# LoggerAVR.net
KiCad netlist of a schematic drawn in EAGLE
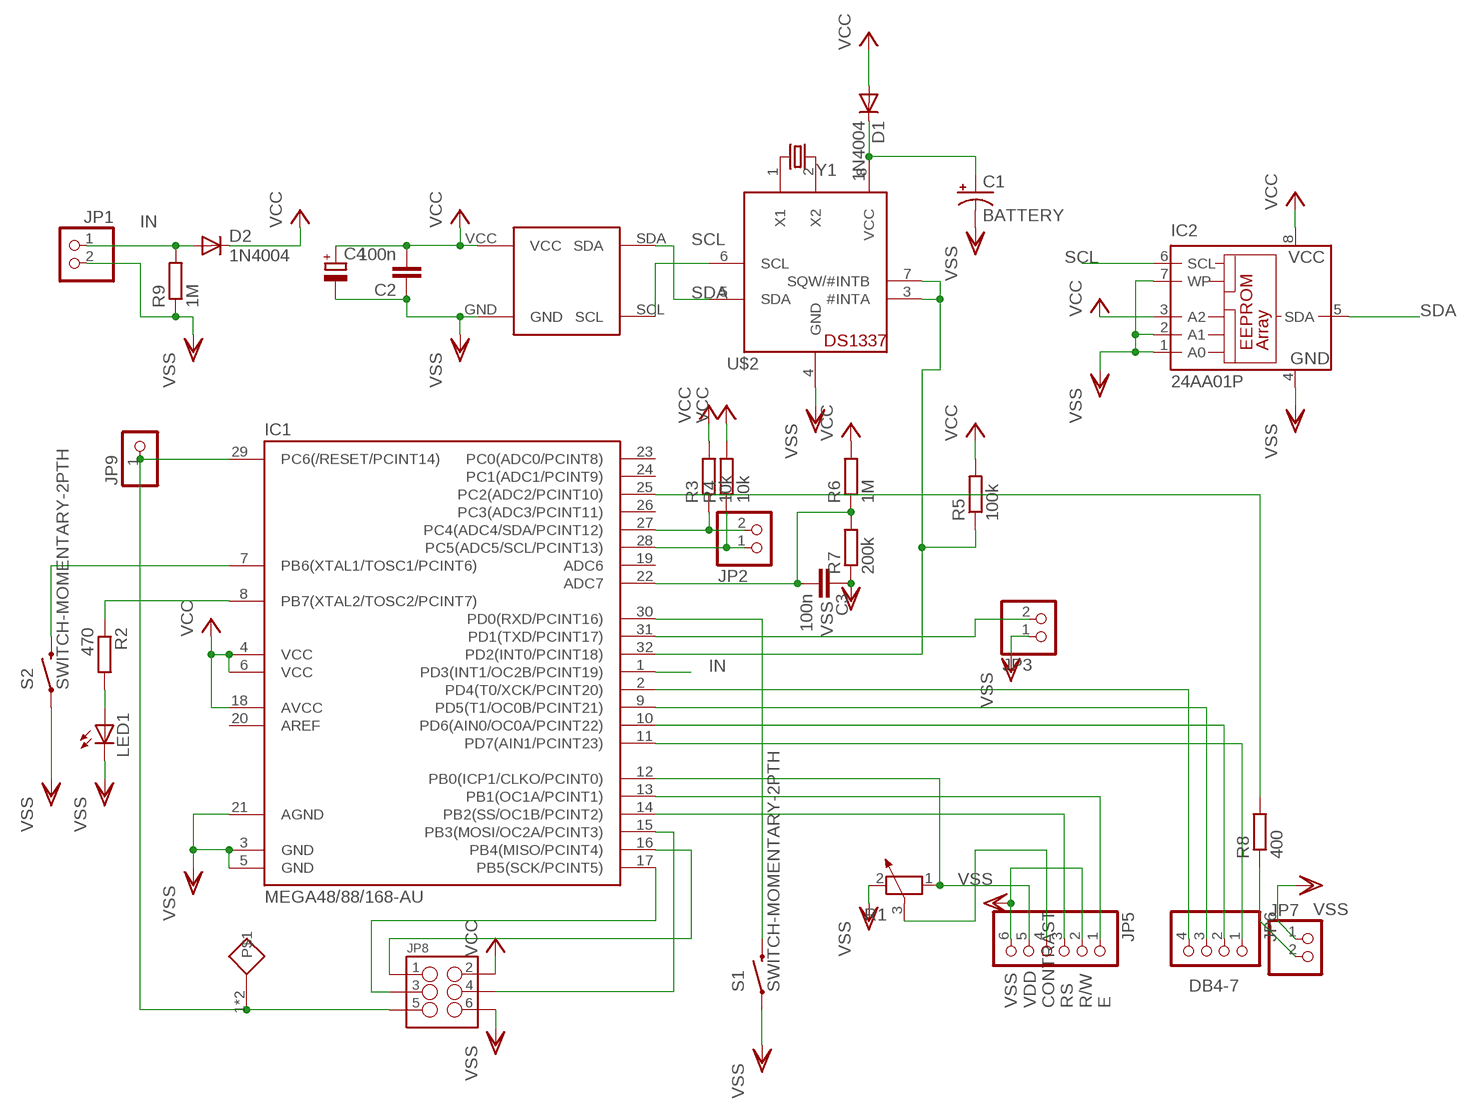
[diagram p0: schematic, sheet 1]

(export (version "E")
  (design (tool "Eeschema 10.0.6"))
  (components
    (comp (ref "C1")
      (value "BATTERY")
      (footprint "eagle-import:ETR2")
      (libsource (lib "eagle-import") (part "CPOL-USETR2"))
    )
    (comp (ref "C2")
      (value "100n")
      (footprint "eagle-import:C1206")
      (libsource (lib "eagle-import") (part "C-EUC1206"))
    )
    (comp (ref "C3")
      (value "100n")
      (footprint "eagle-import:C1206")
      (libsource (lib "eagle-import") (part "C-EUC1206"))
    )
    (comp (ref "C4")
      (value "CPOL-EUE22-9AXIAL")
      (footprint "eagle-import:E22-9")
      (libsource (lib "eagle-import") (part "CPOL-EUE22-9AXIAL"))
    )
    (comp (ref "D1")
      (value "1N4004")
      (footprint "eagle-import:DO41-10")
      (libsource (lib "eagle-import") (part "1N4004"))
    )
    (comp (ref "D2")
      (value "1N4004")
      (footprint "eagle-import:DO41-10")
      (libsource (lib "eagle-import") (part "1N4004"))
    )
    (comp (ref "IC1")
      (value "MEGA48/88/168-AU")
      (footprint "eagle-import:TQFP32-08")
      (libsource (lib "eagle-import") (part "MEGA48/88/168-AU"))
    )
    (comp (ref "IC2")
      (value "24AA01P")
      (footprint "eagle-import:DIL8")
      (libsource (lib "eagle-import") (part "24PAA01"))
    )
    (comp (ref "JP1")
      (value "PINHD-1X2")
      (footprint "eagle-import:1X02")
      (libsource (lib "eagle-import") (part "PINHD-1X2"))
    )
    (comp (ref "JP2")
      (value "PINHD-1X2")
      (footprint "eagle-import:1X02")
      (libsource (lib "eagle-import") (part "PINHD-1X2"))
    )
    (comp (ref "JP3")
      (value "PINHD-1X2")
      (footprint "eagle-import:1X02")
      (libsource (lib "eagle-import") (part "PINHD-1X2"))
    )
    (comp (ref "JP5")
      (value "PINHD-1X6")
      (footprint "eagle-import:1X06")
      (libsource (lib "eagle-import") (part "PINHD-1X6"))
    )
    (comp (ref "JP6")
      (value "PINHD-1X4")
      (footprint "eagle-import:1X04")
      (libsource (lib "eagle-import") (part "PINHD-1X4"))
    )
    (comp (ref "JP7")
      (value "PINHD-1X2")
      (footprint "eagle-import:1X02")
      (libsource (lib "eagle-import") (part "PINHD-1X2"))
    )
    (comp (ref "JP8")
      (value "M03X2SHROUD")
      (footprint "eagle-import:2X3-SHROUDED")
      (libsource (lib "eagle-import") (part "M03X2SHROUD"))
    )
    (comp (ref "JP9")
      (value "PINHD-1X1")
      (footprint "eagle-import:1X01")
      (libsource (lib "eagle-import") (part "PINHD-1X1"))
    )
    (comp (ref "LED1")
      (value "LEDSML1206")
      (footprint "eagle-import:SML1206")
      (libsource (lib "eagle-import") (part "LEDSML1206"))
    )
    (comp (ref "R1")
      (value "POTENTIOMETER_PT-10")
      (footprint "eagle-import:PT-10")
      (libsource (lib "eagle-import") (part "POTENTIOMETER_PT-10"))
    )
    (comp (ref "R2")
      (value "470")
      (footprint "eagle-import:M1206")
      (libsource (lib "eagle-import") (part "R-EU_M1206"))
    )
    (comp (ref "R3")
      (value "10k")
      (footprint "eagle-import:M1206")
      (libsource (lib "eagle-import") (part "R-EU_M1206"))
    )
    (comp (ref "R4")
      (value "10k")
      (footprint "eagle-import:M1206")
      (libsource (lib "eagle-import") (part "R-EU_M1206"))
    )
    (comp (ref "R5")
      (value "100k")
      (footprint "eagle-import:M1206")
      (libsource (lib "eagle-import") (part "R-EU_M1206"))
    )
    (comp (ref "R6")
      (value "1M")
      (footprint "eagle-import:M1206")
      (libsource (lib "eagle-import") (part "R-EU_M1206"))
    )
    (comp (ref "R7")
      (value "200k")
      (footprint "eagle-import:M1206")
      (libsource (lib "eagle-import") (part "R-EU_M1206"))
    )
    (comp (ref "R8")
      (value "400")
      (footprint "eagle-import:M1206")
      (libsource (lib "eagle-import") (part "R-EU_M1206"))
    )
    (comp (ref "R9")
      (value "1M")
      (footprint "eagle-import:M1206")
      (libsource (lib "eagle-import") (part "R-EU_M1206"))
    )
    (comp (ref "S1")
      (value "SWITCH-MOMENTARY-2PTH")
      (footprint "eagle-import:TACTILE-PTH")
      (libsource (lib "eagle-import") (part "SWITCH-MOMENTARY-2PTH"))
    )
    (comp (ref "S2")
      (value "SWITCH-MOMENTARY-2PTH")
      (footprint "eagle-import:TACTILE-PTH")
      (libsource (lib "eagle-import") (part "SWITCH-MOMENTARY-2PTH"))
    )
    (comp (ref "U$1")
      (value "HYT939")
      (footprint "eagle-import:TO39")
      (libsource (lib "eagle-import") (part "HYT939"))
    )
    (comp (ref "U$2")
      (value "DS1337")
      (footprint "eagle-import:DIL08-ROUND")
      (libsource (lib "eagle-import") (part "DS1337"))
    )
    (comp (ref "U$3")
      (value "0 - Jump")
      (footprint "eagle-import:R1206")
      (libsource (lib "eagle-import") (part "O-OHMJUMPER"))
    )
    (comp (ref "Y1")
      (value "CRYSTAL32-SMD")
      (footprint "eagle-import:CRYSTAL-32KHZ-SMD")
      (libsource (lib "eagle-import") (part "CRYSTAL32-SMD"))
    )
  )
  (nets
    (net (code "1") (name "/IN") (class "Default")
      (node (ref "D2") (pin "A") (pinfunction "A_A") (pintype "passive"))
      (node (ref "IC1") (pin "1") (pinfunction "PD3(INT1/OC2B/PCINT19)_1") (pintype "bidirectional"))
      (node (ref "JP1") (pin "1") (pinfunction "1_1") (pintype "passive"))
      (node (ref "R9") (pin "2") (pinfunction "2_2") (pintype "passive"))
    )
    (net (code "2") (name "/SCL") (class "Default")
      (node (ref "IC1") (pin "28") (pinfunction "PC5(ADC5/SCL/PCINT13)_28") (pintype "bidirectional"))
      (node (ref "IC2") (pin "6") (pinfunction "SCL_6") (pintype "input"))
      (node (ref "JP2") (pin "1") (pinfunction "1_1") (pintype "passive"))
      (node (ref "R4") (pin "1") (pinfunction "1_1") (pintype "passive"))
      (node (ref "U$1") (pin "SCL") (pinfunction "SCL_SCL") (pintype "bidirectional"))
      (node (ref "U$2") (pin "6") (pinfunction "SCL_6") (pintype "bidirectional"))
    )
    (net (code "3") (name "/SDA") (class "Default")
      (node (ref "IC1") (pin "27") (pinfunction "PC4(ADC4/SDA/PCINT12)_27") (pintype "bidirectional"))
      (node (ref "IC2") (pin "5") (pinfunction "SDA_5") (pintype "bidirectional"))
      (node (ref "JP2") (pin "2") (pinfunction "2_2") (pintype "passive"))
      (node (ref "R3") (pin "1") (pinfunction "1_1") (pintype "passive"))
      (node (ref "U$1") (pin "SDA") (pinfunction "SDA_SDA") (pintype "bidirectional"))
      (node (ref "U$2") (pin "5") (pinfunction "SDA_5") (pintype "bidirectional"))
    )
    (net (code "4") (name "Net-(IC1-ADC7)") (class "Default")
      (node (ref "C3") (pin "2") (pinfunction "2_2") (pintype "passive"))
      (node (ref "IC1") (pin "22") (pinfunction "ADC7_22") (pintype "passive"))
      (node (ref "R6") (pin "1") (pinfunction "1_1") (pintype "passive"))
      (node (ref "R7") (pin "2") (pinfunction "2_2") (pintype "passive"))
    )
    (net (code "5") (name "Net-(IC1-PB0(ICP1{slash}CLKO{slash}PCINT0))") (class "Default")
      (node (ref "IC1") (pin "12") (pinfunction "PB0(ICP1/CLKO/PCINT0)_12") (pintype "bidirectional"))
      (node (ref "JP5") (pin "5") (pinfunction "5_5") (pintype "passive"))
      (node (ref "R1") (pin "1") (pinfunction "1_1") (pintype "passive"))
    )
    (net (code "6") (name "Net-(IC1-PB1(OC1A{slash}PCINT1))") (class "Default")
      (node (ref "IC1") (pin "13") (pinfunction "PB1(OC1A/PCINT1)_13") (pintype "bidirectional"))
      (node (ref "JP5") (pin "1") (pinfunction "1_1") (pintype "passive"))
    )
    (net (code "7") (name "Net-(IC1-PB2(SS{slash}OC1B{slash}PCINT2))") (class "Default")
      (node (ref "IC1") (pin "14") (pinfunction "PB2(SS/OC1B/PCINT2)_14") (pintype "bidirectional"))
      (node (ref "JP5") (pin "3") (pinfunction "3_3") (pintype "passive"))
    )
    (net (code "8") (name "Net-(IC1-PB3(MOSI{slash}OC2A{slash}PCINT3))") (class "Default")
      (node (ref "IC1") (pin "15") (pinfunction "PB3(MOSI/OC2A/PCINT3)_15") (pintype "bidirectional"))
      (node (ref "JP8") (pin "4") (pinfunction "4_4") (pintype "bidirectional"))
    )
    (net (code "9") (name "Net-(IC1-PB4(MISO{slash}PCINT4))") (class "Default")
      (node (ref "IC1") (pin "16") (pinfunction "PB4(MISO/PCINT4)_16") (pintype "bidirectional"))
      (node (ref "JP8") (pin "1") (pinfunction "1_1") (pintype "bidirectional"))
    )
    (net (code "10") (name "Net-(IC1-PB5(SCK{slash}PCINT5))") (class "Default")
      (node (ref "IC1") (pin "17") (pinfunction "PB5(SCK/PCINT5)_17") (pintype "bidirectional"))
      (node (ref "JP8") (pin "3") (pinfunction "3_3") (pintype "bidirectional"))
    )
    (net (code "11") (name "Net-(IC1-PB6(XTAL1{slash}TOSC1{slash}PCINT6))") (class "Default")
      (node (ref "IC1") (pin "7") (pinfunction "PB6(XTAL1/TOSC1/PCINT6)_7") (pintype "bidirectional"))
      (node (ref "S2") (pin "3") (pinfunction "2_3") (pintype "passive"))
      (node (ref "S2") (pin "4") (pinfunction "2_4") (pintype "passive"))
    )
    (net (code "12") (name "Net-(IC1-PB7(XTAL2{slash}TOSC2{slash}PCINT7))") (class "Default")
      (node (ref "IC1") (pin "8") (pinfunction "PB7(XTAL2/TOSC2/PCINT7)_8") (pintype "bidirectional"))
      (node (ref "R2") (pin "1") (pinfunction "1_1") (pintype "passive"))
    )
    (net (code "13") (name "Net-(IC1-PC2(ADC2{slash}PCINT10))") (class "Default")
      (node (ref "IC1") (pin "25") (pinfunction "PC2(ADC2/PCINT10)_25") (pintype "bidirectional"))
      (node (ref "R8") (pin "2") (pinfunction "2_2") (pintype "passive"))
    )
    (net (code "14") (name "Net-(IC1-PC6({slash}RESET{slash}PCINT14))") (class "Default")
      (node (ref "IC1") (pin "29") (pinfunction "PC6(/RESET/PCINT14)_29") (pintype "bidirectional"))
      (node (ref "JP8") (pin "5") (pinfunction "5_5") (pintype "bidirectional"))
      (node (ref "JP9") (pin "1") (pinfunction "1_1") (pintype "passive"))
      (node (ref "U$3") (pin "1") (pinfunction "P$1_1") (pintype "bidirectional"))
      (node (ref "U$3") (pin "2") (pinfunction "P$1_2") (pintype "bidirectional"))
    )
    (net (code "15") (name "Net-(IC1-PD0(RXD{slash}PCINT16))") (class "Default")
      (node (ref "IC1") (pin "30") (pinfunction "PD0(RXD/PCINT16)_30") (pintype "bidirectional"))
      (node (ref "S1") (pin "3") (pinfunction "2_3") (pintype "passive"))
      (node (ref "S1") (pin "4") (pinfunction "2_4") (pintype "passive"))
    )
    (net (code "16") (name "Net-(IC1-PD1(TXD{slash}PCINT17))") (class "Default")
      (node (ref "IC1") (pin "31") (pinfunction "PD1(TXD/PCINT17)_31") (pintype "bidirectional"))
      (node (ref "JP3") (pin "2") (pinfunction "2_2") (pintype "passive"))
    )
    (net (code "17") (name "Net-(IC1-PD2(INT0{slash}PCINT18))") (class "Default")
      (node (ref "IC1") (pin "32") (pinfunction "PD2(INT0/PCINT18)_32") (pintype "bidirectional"))
      (node (ref "R5") (pin "1") (pinfunction "1_1") (pintype "passive"))
      (node (ref "U$2") (pin "3") (pinfunction "#INTA_3") (pintype "output"))
      (node (ref "U$2") (pin "7") (pinfunction "SQW/#INTB_7") (pintype "output"))
    )
    (net (code "18") (name "Net-(IC1-PD4(T0{slash}XCK{slash}PCINT20))") (class "Default")
      (node (ref "IC1") (pin "2") (pinfunction "PD4(T0/XCK/PCINT20)_2") (pintype "bidirectional"))
      (node (ref "JP6") (pin "4") (pinfunction "4_4") (pintype "passive"))
    )
    (net (code "19") (name "Net-(IC1-PD5(T1{slash}OC0B{slash}PCINT21))") (class "Default")
      (node (ref "IC1") (pin "9") (pinfunction "PD5(T1/OC0B/PCINT21)_9") (pintype "bidirectional"))
      (node (ref "JP6") (pin "3") (pinfunction "3_3") (pintype "passive"))
    )
    (net (code "20") (name "Net-(IC1-PD6(AIN0{slash}OC0A{slash}PCINT22))") (class "Default")
      (node (ref "IC1") (pin "10") (pinfunction "PD6(AIN0/OC0A/PCINT22)_10") (pintype "bidirectional"))
      (node (ref "JP6") (pin "2") (pinfunction "2_2") (pintype "passive"))
    )
    (net (code "21") (name "Net-(IC1-PD7(AIN1{slash}PCINT23))") (class "Default")
      (node (ref "IC1") (pin "11") (pinfunction "PD7(AIN1/PCINT23)_11") (pintype "bidirectional"))
      (node (ref "JP6") (pin "1") (pinfunction "1_1") (pintype "passive"))
    )
    (net (code "22") (name "Net-(JP5-Pad4)") (class "Default")
      (node (ref "JP5") (pin "4") (pinfunction "4_4") (pintype "passive"))
      (node (ref "R1") (pin "3") (pinfunction "3_3") (pintype "passive"))
    )
    (net (code "23") (name "Net-(JP7-Pad2)") (class "Default")
      (node (ref "JP7") (pin "2") (pinfunction "2_2") (pintype "passive"))
      (node (ref "R8") (pin "1") (pinfunction "1_1") (pintype "passive"))
    )
    (net (code "24") (name "Net-(LED1-PadA)") (class "Default")
      (node (ref "LED1") (pin "A") (pinfunction "A_A") (pintype "passive"))
      (node (ref "R2") (pin "2") (pinfunction "2_2") (pintype "passive"))
    )
    (net (code "25") (name "Net-(U$2-VCC)") (class "Default")
      (node (ref "C1") (pin "+") (pinfunction "+_+") (pintype "passive"))
      (node (ref "D1") (pin "C") (pinfunction "C_C") (pintype "passive"))
      (node (ref "U$2") (pin "8") (pinfunction "VCC_8") (pintype "power_in"))
    )
    (net (code "26") (name "Net-(U$2-X1)") (class "Default")
      (node (ref "U$2") (pin "1") (pinfunction "X1_1") (pintype "passive"))
      (node (ref "Y1") (pin "X1") (pinfunction "1_X1") (pintype "passive"))
    )
    (net (code "27") (name "Net-(U$2-X2)") (class "Default")
      (node (ref "U$2") (pin "2") (pinfunction "X2_2") (pintype "passive"))
      (node (ref "Y1") (pin "X2") (pinfunction "2_X2") (pintype "passive"))
    )
    (net (code "28") (name "VCC") (class "Default")
      (node (ref "C2") (pin "2") (pinfunction "2_2") (pintype "passive"))
      (node (ref "C4") (pin "+") (pinfunction "+_+") (pintype "passive"))
      (node (ref "D1") (pin "A") (pinfunction "A_A") (pintype "passive"))
      (node (ref "D2") (pin "C") (pinfunction "C_C") (pintype "passive"))
      (node (ref "IC1") (pin "18") (pinfunction "AVCC_18") (pintype "passive"))
      (node (ref "IC1") (pin "4") (pinfunction "VCC_4") (pintype "power_in"))
      (node (ref "IC1") (pin "6") (pinfunction "VCC_6") (pintype "power_in"))
      (node (ref "IC2") (pin "3") (pinfunction "A2_3") (pintype "input"))
      (node (ref "IC2") (pin "8") (pinfunction "VCC_8") (pintype "power_in"))
      (node (ref "JP8") (pin "2") (pinfunction "2_2") (pintype "bidirectional"))
      (node (ref "R3") (pin "2") (pinfunction "2_2") (pintype "passive"))
      (node (ref "R4") (pin "2") (pinfunction "2_2") (pintype "passive"))
      (node (ref "R5") (pin "2") (pinfunction "2_2") (pintype "passive"))
      (node (ref "R6") (pin "2") (pinfunction "2_2") (pintype "passive"))
      (node (ref "U$1") (pin "VCC") (pinfunction "VCC_VCC") (pintype "bidirectional"))
    )
    (net (code "29") (name "VSS") (class "Default")
      (node (ref "C1") (pin "-") (pinfunction "-_-") (pintype "passive"))
      (node (ref "C2") (pin "1") (pinfunction "1_1") (pintype "passive"))
      (node (ref "C3") (pin "1") (pinfunction "1_1") (pintype "passive"))
      (node (ref "C4") (pin "-") (pinfunction "-_-") (pintype "passive"))
      (node (ref "IC1") (pin "21") (pinfunction "AGND_21") (pintype "power_in"))
      (node (ref "IC1") (pin "3") (pinfunction "GND_3") (pintype "power_in"))
      (node (ref "IC1") (pin "5") (pinfunction "GND_5") (pintype "power_in"))
      (node (ref "IC2") (pin "1") (pinfunction "A0_1") (pintype "input"))
      (node (ref "IC2") (pin "2") (pinfunction "A1_2") (pintype "input"))
      (node (ref "IC2") (pin "4") (pinfunction "GND_4") (pintype "power_in"))
      (node (ref "IC2") (pin "7") (pinfunction "WP_7") (pintype "input"))
      (node (ref "JP1") (pin "2") (pinfunction "2_2") (pintype "passive"))
      (node (ref "JP3") (pin "1") (pinfunction "1_1") (pintype "passive"))
      (node (ref "JP5") (pin "2") (pinfunction "2_2") (pintype "passive"))
      (node (ref "JP5") (pin "6") (pinfunction "6_6") (pintype "passive"))
      (node (ref "JP7") (pin "1") (pinfunction "1_1") (pintype "passive"))
      (node (ref "JP8") (pin "6") (pinfunction "6_6") (pintype "bidirectional"))
      (node (ref "LED1") (pin "C") (pinfunction "C_C") (pintype "passive"))
      (node (ref "R1") (pin "2") (pinfunction "2_2") (pintype "passive"))
      (node (ref "R7") (pin "1") (pinfunction "1_1") (pintype "passive"))
      (node (ref "R9") (pin "1") (pinfunction "1_1") (pintype "passive"))
      (node (ref "S1") (pin "1") (pinfunction "1_1") (pintype "passive"))
      (node (ref "S1") (pin "2") (pinfunction "1_2") (pintype "passive"))
      (node (ref "S2") (pin "1") (pinfunction "1_1") (pintype "passive"))
      (node (ref "S2") (pin "2") (pinfunction "1_2") (pintype "passive"))
      (node (ref "U$1") (pin "GND") (pinfunction "GND_GND") (pintype "bidirectional"))
      (node (ref "U$2") (pin "4") (pinfunction "GND_4") (pintype "power_in"))
    )
    (net (code "30") (name "unconnected-(IC1-ADC6-Pad19)") (class "Default")
      (node (ref "IC1") (pin "19") (pinfunction "ADC6_19") (pintype "passive"))
    )
    (net (code "31") (name "unconnected-(IC1-AREF-Pad20)") (class "Default")
      (node (ref "IC1") (pin "20") (pinfunction "AREF_20") (pintype "passive"))
    )
    (net (code "32") (name "unconnected-(IC1-PC0(ADC0{slash}PCINT8)-Pad23)") (class "Default")
      (node (ref "IC1") (pin "23") (pinfunction "PC0(ADC0/PCINT8)_23") (pintype "bidirectional"))
    )
    (net (code "33") (name "unconnected-(IC1-PC1(ADC1{slash}PCINT9)-Pad24)") (class "Default")
      (node (ref "IC1") (pin "24") (pinfunction "PC1(ADC1/PCINT9)_24") (pintype "bidirectional"))
    )
    (net (code "34") (name "unconnected-(IC1-PC3(ADC3{slash}PCINT11)-Pad26)") (class "Default")
      (node (ref "IC1") (pin "26") (pinfunction "PC3(ADC3/PCINT11)_26") (pintype "bidirectional"))
    )
  )
)
